# design.net
KiCad netlist of a schematic drawn in Altium Designer
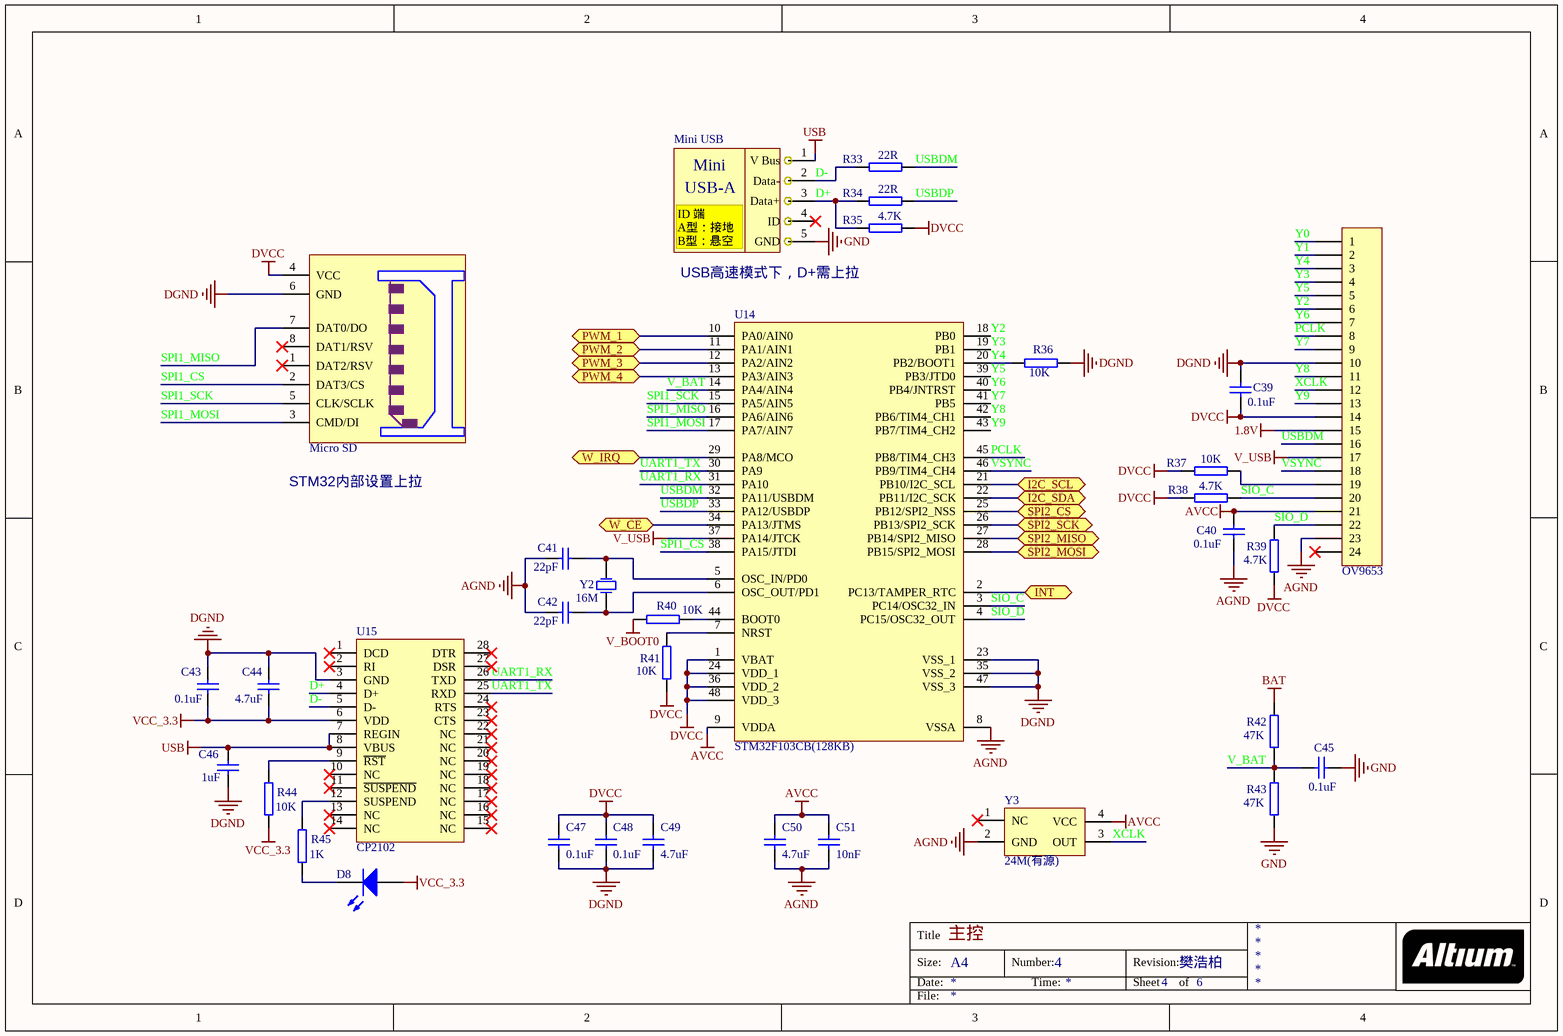
[diagram p0: 主控.SchDoc]

(export (version "E")
  (design (tool "Eeschema 10.0.6"))
  (components
    (comp (ref "C39") (value "0.1uF") (footprint "CAP-0402") (libsource (lib "Connectors") (part "Cap")))
    (comp (ref "C40") (value "0.1uF") (footprint "CAP-0402") (libsource (lib "Connectors") (part "Cap")))
    (comp (ref "C41") (value "22pF") (footprint "CAP-0402") (libsource (lib "Connectors") (part "Cap")))
    (comp (ref "C42") (value "22pF") (footprint "CAP-0402") (libsource (lib "Connectors") (part "Cap")))
    (comp (ref "C43") (value "0.1uF") (footprint "CAP-0402") (libsource (lib "Connectors") (part "Cap")))
    (comp (ref "C44") (value "4.7uF") (footprint "CAP-0402") (libsource (lib "Connectors") (part "Cap")))
    (comp (ref "C45") (value "0.1uF") (footprint "CAP-0402") (libsource (lib "Connectors") (part "Cap")))
    (comp (ref "C46") (value "1uF") (footprint "CAP-0402") (libsource (lib "Connectors") (part "Cap")))
    (comp (ref "C47") (value "0.1uF") (footprint "CAP-0402") (libsource (lib "Connectors") (part "Cap")))
    (comp (ref "C48") (value "0.1uF") (footprint "CAP-0402") (libsource (lib "Connectors") (part "Cap")))
    (comp (ref "C49") (value "4.7uF") (footprint "CAP-0402") (libsource (lib "Connectors") (part "Cap")))
    (comp (ref "C50") (value "4.7uF") (footprint "CAP-0402") (libsource (lib "Connectors") (part "Cap")))
    (comp (ref "C51") (value "10nF") (footprint "CAP-0402") (libsource (lib "Connectors") (part "Cap")))
    (comp (ref "D8") (value "LED") (footprint "LED-GRE-0603") (libsource (lib "Connectors") (part "LED")))
    (comp (ref "Micro SD")
      (value "SD")
      (footprint "Micro-SD")
      (libsource (lib "Connectors") (part "Micro-SD"))
    )
    (comp (ref "Mini USB")
      (value "Mini-USB-A")
      (footprint "Mini-USB(a)-SMD")
      (libsource (lib "Connectors") (part "Mini-USB-A"))
    )
    (comp (ref "OV9653")
      (value "CON-24X1")
      (footprint "HEADER-FPC-ZIF-SMD-Horizontal-0.5-24")
      (libsource (lib "Connectors-Header") (part "CON-24X1"))
    )
    (comp (ref "R33") (value "22R") (footprint "RES-0402") (libsource (lib "Connectors") (part "Res")))
    (comp (ref "R34") (value "22R") (footprint "RES-0402") (libsource (lib "Connectors") (part "Res")))
    (comp (ref "R35") (value "4.7K") (footprint "RES-0402") (libsource (lib "Connectors") (part "Res")))
    (comp (ref "R36") (value "10K") (footprint "RES-0402") (libsource (lib "Connectors") (part "Res")))
    (comp (ref "R37") (value "10K") (footprint "RES-0402") (libsource (lib "Connectors") (part "Res")))
    (comp (ref "R38") (value "4.7K") (footprint "RES-0402") (libsource (lib "Connectors") (part "Res")))
    (comp (ref "R39") (value "4.7K") (footprint "RES-0402") (libsource (lib "Connectors") (part "Res")))
    (comp (ref "R40") (value "10K") (footprint "RES-0402") (libsource (lib "Connectors") (part "Res")))
    (comp (ref "R41") (value "10K") (footprint "RES-0402") (libsource (lib "Connectors") (part "Res")))
    (comp (ref "R42") (value "47K") (footprint "RES-0402") (libsource (lib "Connectors") (part "Res")))
    (comp (ref "R43") (value "47K") (footprint "RES-0402") (libsource (lib "Connectors") (part "Res")))
    (comp (ref "R44") (value "10K") (footprint "RES-0402") (libsource (lib "Connectors") (part "Res")))
    (comp (ref "R45") (value "1K") (footprint "RES-0402") (libsource (lib "Connectors") (part "Res")))
    (comp (ref "U14")
      (value "STM32F103CB(128KB)")
      (footprint "QFN-48-7x7mm")
      (libsource (lib "Devices") (part "STM32F103-48P"))
    )
    (comp (ref "U15") (value "CP2102") (footprint "QFN-28-5x5mm") (libsource (lib "Devices") (part "CP2102")))
    (comp (ref "Y2") (value "16M") (footprint "XTAL-OSC-3225") (libsource (lib "Connectors") (part "XTAL")))
    (comp (ref "Y3")
      (value "24M(有源)")
      (footprint "XTAL-OSC-3225")
      (libsource (lib "Connectors") (part "XTAL-OSC"))
    )
  )
  (nets
    (net (code "1") (name "/D+") (class "Default")
      (node (ref "Mini USB") (pin "3") (pinfunction "Data+_3") (pintype "passive"))
      (node (ref "R34") (pin "1") (pinfunction "1_1") (pintype "passive"))
      (node (ref "R35") (pin "1") (pinfunction "1_1") (pintype "passive"))
      (node (ref "U15") (pin "4") (pinfunction "D+_4") (pintype "passive"))
    )
    (net (code "2") (name "/D-") (class "Default")
      (node (ref "Mini USB") (pin "2") (pinfunction "Data-_2") (pintype "passive"))
      (node (ref "R33") (pin "1") (pinfunction "1_1") (pintype "passive"))
      (node (ref "U15") (pin "5") (pinfunction "D-_5") (pintype "passive"))
    )
    (net (code "3") (name "/I2C_SCL") (class "Default")
      (node (ref "U14") (pin "21") (pinfunction "PB10/I2C_SCL_21") (pintype "passive"))
    )
    (net (code "4") (name "/I2C_SDA") (class "Default")
      (node (ref "U14") (pin "22") (pinfunction "PB11/I2C_SCK_22") (pintype "passive"))
    )
    (net (code "5") (name "/INT") (class "Default")
      (node (ref "U14") (pin "2") (pinfunction "PC13/TAMPER_RTC_2") (pintype "passive"))
    )
    (net (code "6") (name "/PCLK") (class "Default")
      (node (ref "OV9653") (pin "8") (pinfunction "8_8") (pintype "passive"))
      (node (ref "U14") (pin "45") (pinfunction "PB8/TIM4_CH3_45") (pintype "passive"))
    )
    (net (code "7") (name "/PWM_1") (class "Default")
      (node (ref "U14") (pin "10") (pinfunction "PA0/AIN0_10") (pintype "passive"))
    )
    (net (code "8") (name "/PWM_2") (class "Default")
      (node (ref "U14") (pin "11") (pinfunction "PA1/AIN1_11") (pintype "passive"))
    )
    (net (code "9") (name "/PWM_3") (class "Default")
      (node (ref "U14") (pin "12") (pinfunction "PA2/AIN2_12") (pintype "passive"))
    )
    (net (code "10") (name "/PWM_4") (class "Default")
      (node (ref "U14") (pin "13") (pinfunction "PA3/AIN3_13") (pintype "passive"))
    )
    (net (code "11") (name "/SIO_C") (class "Default")
      (node (ref "OV9653") (pin "20") (pinfunction "20_20") (pintype "passive"))
      (node (ref "R38") (pin "1") (pinfunction "1_1") (pintype "passive"))
      (node (ref "U14") (pin "3") (pinfunction "PC14/OSC32_IN_3") (pintype "passive"))
    )
    (net (code "12") (name "/SIO_D") (class "Default")
      (node (ref "OV9653") (pin "22") (pinfunction "22_22") (pintype "passive"))
      (node (ref "R39") (pin "1") (pinfunction "1_1") (pintype "passive"))
      (node (ref "U14") (pin "4") (pinfunction "PC15/OSC32_OUT_4") (pintype "passive"))
    )
    (net (code "13") (name "/SPI1_CS") (class "Default")
      (node (ref "Micro SD") (pin "2") (pinfunction "DAT3/CS_2") (pintype "passive"))
      (node (ref "U14") (pin "38") (pinfunction "PA15/JTDI_38") (pintype "passive"))
    )
    (net (code "14") (name "/SPI1_MISO") (class "Default")
      (node (ref "Micro SD") (pin "7") (pinfunction "DAT0/DO_7") (pintype "passive"))
      (node (ref "U14") (pin "16") (pinfunction "PA6/AIN6_16") (pintype "passive"))
    )
    (net (code "15") (name "/SPI1_MOSI") (class "Default")
      (node (ref "Micro SD") (pin "3") (pinfunction "CMD/DI_3") (pintype "passive"))
      (node (ref "U14") (pin "17") (pinfunction "PA7/AIN7_17") (pintype "passive"))
    )
    (net (code "16") (name "/SPI1_SCK") (class "Default")
      (node (ref "Micro SD") (pin "5") (pinfunction "CLK/SCLK_5") (pintype "passive"))
      (node (ref "U14") (pin "15") (pinfunction "PA5/AIN5_15") (pintype "passive"))
    )
    (net (code "17") (name "/SPI2_CS") (class "Default")
      (node (ref "U14") (pin "25") (pinfunction "PB12/SPI2_NSS_25") (pintype "passive"))
    )
    (net (code "18") (name "/SPI2_MISO") (class "Default")
      (node (ref "U14") (pin "27") (pinfunction "PB14/SPI2_MISO_27") (pintype "passive"))
    )
    (net (code "19") (name "/SPI2_MOSI") (class "Default")
      (node (ref "U14") (pin "28") (pinfunction "PB15/SPI2_MOSI_28") (pintype "passive"))
    )
    (net (code "20") (name "/SPI2_SCK") (class "Default")
      (node (ref "U14") (pin "26") (pinfunction "PB13/SPI2_SCK_26") (pintype "passive"))
    )
    (net (code "21") (name "/UART1_RX") (class "Default")
      (node (ref "U14") (pin "31") (pinfunction "PA10_31") (pintype "passive"))
      (node (ref "U15") (pin "26") (pinfunction "TXD_26") (pintype "passive"))
    )
    (net (code "22") (name "/UART1_TX") (class "Default")
      (node (ref "U14") (pin "30") (pinfunction "PA9_30") (pintype "passive"))
      (node (ref "U15") (pin "25") (pinfunction "RXD_25") (pintype "passive"))
    )
    (net (code "23") (name "/USBDM") (class "Default")
      (node (ref "OV9653") (pin "16") (pinfunction "16_16") (pintype "passive"))
      (node (ref "R33") (pin "2") (pinfunction "2_2") (pintype "passive"))
      (node (ref "U14") (pin "32") (pinfunction "PA11/USBDM_32") (pintype "passive"))
    )
    (net (code "24") (name "/USBDP") (class "Default")
      (node (ref "R34") (pin "2") (pinfunction "2_2") (pintype "passive"))
      (node (ref "U14") (pin "33") (pinfunction "PA12/USBDP_33") (pintype "passive"))
    )
    (net (code "25") (name "/VSYNC") (class "Default")
      (node (ref "OV9653") (pin "18") (pinfunction "18_18") (pintype "passive"))
      (node (ref "U14") (pin "46") (pinfunction "PB9/TIM4_CH4_46") (pintype "passive"))
    )
    (net (code "26") (name "/V_BAT") (class "Default")
      (node (ref "C45") (pin "1") (pinfunction "1_1") (pintype "passive"))
      (node (ref "R42") (pin "2") (pinfunction "2_2") (pintype "passive"))
      (node (ref "R43") (pin "1") (pinfunction "1_1") (pintype "passive"))
      (node (ref "U14") (pin "14") (pinfunction "PA4/AIN4_14") (pintype "passive"))
    )
    (net (code "27") (name "/W_CE") (class "Default")
      (node (ref "U14") (pin "34") (pinfunction "PA13/JTMS_34") (pintype "passive"))
    )
    (net (code "28") (name "/W_IRQ") (class "Default")
      (node (ref "U14") (pin "29") (pinfunction "PA8/MCO_29") (pintype "passive"))
    )
    (net (code "29") (name "/XCLK") (class "Default")
      (node (ref "OV9653") (pin "12") (pinfunction "12_12") (pintype "passive"))
      (node (ref "Y3") (pin "3") (pinfunction "OUT_3") (pintype "passive"))
    )
    (net (code "30") (name "/Y0") (class "Default")
      (node (ref "OV9653") (pin "1") (pinfunction "1_1") (pintype "passive"))
    )
    (net (code "31") (name "/Y1") (class "Default")
      (node (ref "OV9653") (pin "2") (pinfunction "2_2") (pintype "passive"))
    )
    (net (code "32") (name "/Y2") (class "Default")
      (node (ref "OV9653") (pin "6") (pinfunction "6_6") (pintype "passive"))
      (node (ref "U14") (pin "18") (pinfunction "PB0_18") (pintype "passive"))
    )
    (net (code "33") (name "/Y3") (class "Default")
      (node (ref "OV9653") (pin "4") (pinfunction "4_4") (pintype "passive"))
      (node (ref "U14") (pin "19") (pinfunction "PB1_19") (pintype "passive"))
    )
    (net (code "34") (name "/Y4") (class "Default")
      (node (ref "OV9653") (pin "3") (pinfunction "3_3") (pintype "passive"))
      (node (ref "R36") (pin "2") (pinfunction "2_2") (pintype "passive"))
      (node (ref "U14") (pin "20") (pinfunction "PB2/BOOT1_20") (pintype "passive"))
    )
    (net (code "35") (name "/Y5") (class "Default")
      (node (ref "OV9653") (pin "5") (pinfunction "5_5") (pintype "passive"))
      (node (ref "U14") (pin "39") (pinfunction "PB3/JTD0_39") (pintype "passive"))
    )
    (net (code "36") (name "/Y6") (class "Default")
      (node (ref "OV9653") (pin "7") (pinfunction "7_7") (pintype "passive"))
      (node (ref "U14") (pin "40") (pinfunction "PB4/JNTRST_40") (pintype "passive"))
    )
    (net (code "37") (name "/Y7") (class "Default")
      (node (ref "OV9653") (pin "9") (pinfunction "9_9") (pintype "passive"))
      (node (ref "U14") (pin "41") (pinfunction "PB5_41") (pintype "passive"))
    )
    (net (code "38") (name "/Y8") (class "Default")
      (node (ref "OV9653") (pin "11") (pinfunction "11_11") (pintype "passive"))
      (node (ref "U14") (pin "42") (pinfunction "PB6/TIM4_CH1_42") (pintype "passive"))
    )
    (net (code "39") (name "/Y9") (class "Default")
      (node (ref "OV9653") (pin "13") (pinfunction "13_13") (pintype "passive"))
      (node (ref "U14") (pin "43") (pinfunction "PB7/TIM4_CH2_43") (pintype "passive"))
    )
    (net (code "40") (name "1.8V") (class "Default")
      (node (ref "OV9653") (pin "15") (pinfunction "15_15") (pintype "passive"))
    )
    (net (code "41") (name "AGND") (class "Default")
      (node (ref "C40") (pin "2") (pinfunction "2_2") (pintype "passive"))
      (node (ref "C41") (pin "2") (pinfunction "2_2") (pintype "passive"))
      (node (ref "C42") (pin "2") (pinfunction "2_2") (pintype "passive"))
      (node (ref "C50") (pin "2") (pinfunction "2_2") (pintype "passive"))
      (node (ref "C51") (pin "2") (pinfunction "2_2") (pintype "passive"))
      (node (ref "OV9653") (pin "23") (pinfunction "23_23") (pintype "passive"))
      (node (ref "U14") (pin "8") (pinfunction "VSSA_8") (pintype "passive"))
      (node (ref "Y3") (pin "2") (pinfunction "GND_2") (pintype "passive"))
    )
    (net (code "42") (name "AVCC") (class "Default")
      (node (ref "C40") (pin "1") (pinfunction "1_1") (pintype "passive"))
      (node (ref "C50") (pin "1") (pinfunction "1_1") (pintype "passive"))
      (node (ref "C51") (pin "1") (pinfunction "1_1") (pintype "passive"))
      (node (ref "OV9653") (pin "21") (pinfunction "21_21") (pintype "passive"))
      (node (ref "U14") (pin "9") (pinfunction "VDDA_9") (pintype "passive"))
      (node (ref "Y3") (pin "4") (pinfunction "VCC_4") (pintype "passive"))
    )
    (net (code "43") (name "BAT") (class "Default")
      (node (ref "R42") (pin "1") (pinfunction "1_1") (pintype "passive"))
    )
    (net (code "44") (name "DGND") (class "Default")
      (node (ref "C39") (pin "1") (pinfunction "1_1") (pintype "passive"))
      (node (ref "C43") (pin "2") (pinfunction "2_2") (pintype "passive"))
      (node (ref "C44") (pin "2") (pinfunction "2_2") (pintype "passive"))
      (node (ref "C46") (pin "1") (pinfunction "1_1") (pintype "passive"))
      (node (ref "C47") (pin "2") (pinfunction "2_2") (pintype "passive"))
      (node (ref "C48") (pin "2") (pinfunction "2_2") (pintype "passive"))
      (node (ref "C49") (pin "2") (pinfunction "2_2") (pintype "passive"))
      (node (ref "Micro SD") (pin "6") (pinfunction "GND_6") (pintype "passive"))
      (node (ref "OV9653") (pin "10") (pinfunction "10_10") (pintype "passive"))
      (node (ref "R36") (pin "1") (pinfunction "1_1") (pintype "passive"))
      (node (ref "U14") (pin "23") (pinfunction "VSS_1_23") (pintype "passive"))
      (node (ref "U14") (pin "35") (pinfunction "VSS_2_35") (pintype "passive"))
      (node (ref "U14") (pin "47") (pinfunction "VSS_3_47") (pintype "passive"))
      (node (ref "U15") (pin "3") (pinfunction "GND_3") (pintype "passive"))
    )
    (net (code "45") (name "DVCC") (class "Default")
      (node (ref "C39") (pin "2") (pinfunction "2_2") (pintype "passive"))
      (node (ref "C47") (pin "1") (pinfunction "1_1") (pintype "passive"))
      (node (ref "C48") (pin "1") (pinfunction "1_1") (pintype "passive"))
      (node (ref "C49") (pin "1") (pinfunction "1_1") (pintype "passive"))
      (node (ref "Micro SD") (pin "4") (pinfunction "VCC_4") (pintype "passive"))
      (node (ref "OV9653") (pin "14") (pinfunction "14_14") (pintype "passive"))
      (node (ref "R35") (pin "2") (pinfunction "2_2") (pintype "passive"))
      (node (ref "R37") (pin "2") (pinfunction "2_2") (pintype "passive"))
      (node (ref "R38") (pin "2") (pinfunction "2_2") (pintype "passive"))
      (node (ref "R39") (pin "2") (pinfunction "2_2") (pintype "passive"))
      (node (ref "R41") (pin "1") (pinfunction "1_1") (pintype "passive"))
      (node (ref "U14") (pin "1") (pinfunction "VBAT_1") (pintype "passive"))
      (node (ref "U14") (pin "24") (pinfunction "VDD_1_24") (pintype "passive"))
      (node (ref "U14") (pin "36") (pinfunction "VDD_2_36") (pintype "passive"))
      (node (ref "U14") (pin "48") (pinfunction "VDD_3_48") (pintype "passive"))
    )
    (net (code "46") (name "GND") (class "Default")
      (node (ref "C45") (pin "2") (pinfunction "2_2") (pintype "passive"))
      (node (ref "Mini USB") (pin "5") (pinfunction "GND_5") (pintype "passive"))
      (node (ref "R43") (pin "2") (pinfunction "2_2") (pintype "passive"))
    )
    (net (code "47") (name "Net-(D8-2)") (class "Default")
      (node (ref "D8") (pin "K") (pinfunction "2_K") (pintype "passive"))
      (node (ref "R45") (pin "2") (pinfunction "2_2") (pintype "passive"))
    )
    (net (code "48") (name "Net-(OV9653-Pad19)") (class "Default")
      (node (ref "OV9653") (pin "19") (pinfunction "19_19") (pintype "passive"))
      (node (ref "R37") (pin "1") (pinfunction "1_1") (pintype "passive"))
    )
    (net (code "49") (name "Net-(U14-BOOT0)") (class "Default")
      (node (ref "R40") (pin "2") (pinfunction "2_2") (pintype "passive"))
      (node (ref "U14") (pin "44") (pinfunction "BOOT0_44") (pintype "passive"))
    )
    (net (code "50") (name "Net-(U14-NRST)") (class "Default")
      (node (ref "R41") (pin "2") (pinfunction "2_2") (pintype "passive"))
      (node (ref "U14") (pin "7") (pinfunction "NRST_7") (pintype "passive"))
    )
    (net (code "51") (name "Net-(U14-OSC_IN{slash}PD0)") (class "Default")
      (node (ref "C41") (pin "1") (pinfunction "1_1") (pintype "passive"))
      (node (ref "U14") (pin "5") (pinfunction "OSC_IN/PD0_5") (pintype "passive"))
      (node (ref "Y2") (pin "3") (pinfunction "OSC2_3") (pintype "passive"))
    )
    (net (code "52") (name "Net-(U14-OSC_OUT{slash}PD1)") (class "Default")
      (node (ref "C42") (pin "1") (pinfunction "1_1") (pintype "passive"))
      (node (ref "U14") (pin "6") (pinfunction "OSC_OUT/PD1_6") (pintype "passive"))
      (node (ref "Y2") (pin "1") (pinfunction "OSC1_1") (pintype "passive"))
    )
    (net (code "53") (name "Net-(U15-SUSPEND)") (class "Default")
      (node (ref "R45") (pin "1") (pinfunction "1_1") (pintype "passive"))
      (node (ref "U15") (pin "12") (pinfunction "SUSPEND_12") (pintype "passive"))
    )
    (net (code "54") (name "Net-(U15-~{RST})") (class "Default")
      (node (ref "R44") (pin "1") (pinfunction "1_1") (pintype "passive"))
      (node (ref "U15") (pin "9") (pinfunction "~{RST}_9") (pintype "passive"))
    )
    (net (code "55") (name "USB") (class "Default")
      (node (ref "C46") (pin "2") (pinfunction "2_2") (pintype "passive"))
      (node (ref "Mini USB") (pin "1") (pinfunction "V_Bus_1") (pintype "power_in"))
      (node (ref "U15") (pin "7") (pinfunction "REGIN_7") (pintype "passive"))
      (node (ref "U15") (pin "8") (pinfunction "VBUS_8") (pintype "passive"))
    )
    (net (code "56") (name "VCC_3.3") (class "Default")
      (node (ref "C43") (pin "1") (pinfunction "1_1") (pintype "passive"))
      (node (ref "C44") (pin "1") (pinfunction "1_1") (pintype "passive"))
      (node (ref "D8") (pin "A") (pinfunction "1_A") (pintype "passive"))
      (node (ref "R44") (pin "2") (pinfunction "2_2") (pintype "passive"))
      (node (ref "U15") (pin "6") (pinfunction "VDD_6") (pintype "passive"))
    )
    (net (code "57") (name "V_BOOT0") (class "Default")
      (node (ref "R40") (pin "1") (pinfunction "1_1") (pintype "passive"))
    )
    (net (code "58") (name "V_USB") (class "Default")
      (node (ref "OV9653") (pin "17") (pinfunction "17_17") (pintype "passive"))
      (node (ref "U14") (pin "37") (pinfunction "PA14/JTCK_37") (pintype "passive"))
    )
    (net (code "59") (name "unconnected-(Micro SD-DAT1{slash}RSV-Pad8)") (class "Default")
      (node (ref "Micro SD") (pin "8") (pinfunction "DAT1/RSV_8") (pintype "passive+no_connect"))
    )
    (net (code "60") (name "unconnected-(Micro SD-DAT2{slash}RSV-Pad1)") (class "Default")
      (node (ref "Micro SD") (pin "1") (pinfunction "DAT2/RSV_1") (pintype "passive+no_connect"))
    )
    (net (code "61") (name "unconnected-(Mini USB-ID-Pad4)") (class "Default")
      (node (ref "Mini USB") (pin "4") (pinfunction "ID_4") (pintype "passive+no_connect"))
    )
    (net (code "62") (name "unconnected-(OV9653-Pad24)") (class "Default")
      (node (ref "OV9653") (pin "24") (pinfunction "24_24") (pintype "passive+no_connect"))
    )
    (net (code "63") (name "unconnected-(U15-CTS-Pad23)") (class "Default")
      (node (ref "U15") (pin "23") (pinfunction "CTS_23") (pintype "passive+no_connect"))
    )
    (net (code "64") (name "unconnected-(U15-DCD-Pad1)") (class "Default")
      (node (ref "U15") (pin "1") (pinfunction "DCD_1") (pintype "passive+no_connect"))
    )
    (net (code "65") (name "unconnected-(U15-DSR-Pad27)") (class "Default")
      (node (ref "U15") (pin "27") (pinfunction "DSR_27") (pintype "passive+no_connect"))
    )
    (net (code "66") (name "unconnected-(U15-DTR-Pad28)") (class "Default")
      (node (ref "U15") (pin "28") (pinfunction "DTR_28") (pintype "passive+no_connect"))
    )
    (net (code "67") (name "unconnected-(U15-NC-Pad10)") (class "Default")
      (node (ref "U15") (pin "10") (pinfunction "NC_10") (pintype "passive+no_connect"))
    )
    (net (code "68") (name "unconnected-(U15-NC-Pad13)") (class "Default")
      (node (ref "U15") (pin "13") (pinfunction "NC_13") (pintype "passive+no_connect"))
    )
    (net (code "69") (name "unconnected-(U15-NC-Pad14)") (class "Default")
      (node (ref "U15") (pin "14") (pinfunction "NC_14") (pintype "passive+no_connect"))
    )
    (net (code "70") (name "unconnected-(U15-NC-Pad15)") (class "Default")
      (node (ref "U15") (pin "15") (pinfunction "NC_15") (pintype "passive+no_connect"))
    )
    (net (code "71") (name "unconnected-(U15-NC-Pad16)") (class "Default")
      (node (ref "U15") (pin "16") (pinfunction "NC_16") (pintype "passive+no_connect"))
    )
    (net (code "72") (name "unconnected-(U15-NC-Pad17)") (class "Default")
      (node (ref "U15") (pin "17") (pinfunction "NC_17") (pintype "passive+no_connect"))
    )
    (net (code "73") (name "unconnected-(U15-NC-Pad18)") (class "Default")
      (node (ref "U15") (pin "18") (pinfunction "NC_18") (pintype "passive+no_connect"))
    )
    (net (code "74") (name "unconnected-(U15-NC-Pad19)") (class "Default")
      (node (ref "U15") (pin "19") (pinfunction "NC_19") (pintype "passive+no_connect"))
    )
    (net (code "75") (name "unconnected-(U15-NC-Pad20)") (class "Default")
      (node (ref "U15") (pin "20") (pinfunction "NC_20") (pintype "passive+no_connect"))
    )
    (net (code "76") (name "unconnected-(U15-NC-Pad21)") (class "Default")
      (node (ref "U15") (pin "21") (pinfunction "NC_21") (pintype "passive+no_connect"))
    )
    (net (code "77") (name "unconnected-(U15-NC-Pad22)") (class "Default")
      (node (ref "U15") (pin "22") (pinfunction "NC_22") (pintype "passive+no_connect"))
    )
    (net (code "78") (name "unconnected-(U15-RI-Pad2)") (class "Default")
      (node (ref "U15") (pin "2") (pinfunction "RI_2") (pintype "passive+no_connect"))
    )
    (net (code "79") (name "unconnected-(U15-RTS-Pad24)") (class "Default")
      (node (ref "U15") (pin "24") (pinfunction "RTS_24") (pintype "passive+no_connect"))
    )
    (net (code "80") (name "unconnected-(U15-~{SUSPEND}-Pad11)") (class "Default")
      (node (ref "U15") (pin "11") (pinfunction "~{SUSPEND}_11") (pintype "passive+no_connect"))
    )
    (net (code "81") (name "unconnected-(Y3-NC-Pad1)") (class "Default")
      (node (ref "Y3") (pin "1") (pinfunction "NC_1") (pintype "passive+no_connect"))
    )
  )
)
